# Sensor_Current__INA21X_INA199AX.net
KiCad netlist of a schematic drawn in EAGLE
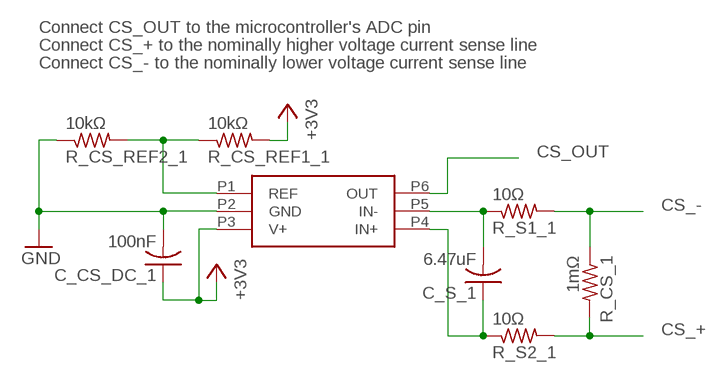
[diagram p0: schematic, sheet 1]

(export (version "E")
  (design (tool "Eeschema 10.0.6"))
  (components
    (comp (ref "CS_1")
      (value "INA21X")
      (footprint "eagle-import:SC70")
      (libsource (lib "eagle-import") (part "INA21X"))
    )
    (comp (ref "C_CS_DC_1")
      (value "100nF")
      (footprint "eagle-import:C0603")
      (libsource (lib "eagle-import") (part "C-USC0603"))
    )
    (comp (ref "C_S_1")
      (value "6.47uF")
      (footprint "eagle-import:C0603")
      (libsource (lib "eagle-import") (part "C-USC0603"))
    )
    (comp (ref "R_CS_1")
      (value "1mΩ")
      (footprint "eagle-import:R1206")
      (libsource (lib "eagle-import") (part "R-US_R1206"))
    )
    (comp (ref "R_CS_REF1_1")
      (value "10kΩ")
      (footprint "eagle-import:R0603")
      (libsource (lib "eagle-import") (part "R-US_R0603"))
    )
    (comp (ref "R_CS_REF2_1")
      (value "10kΩ")
      (footprint "eagle-import:R0603")
      (libsource (lib "eagle-import") (part "R-US_R0603"))
    )
    (comp (ref "R_S1_1")
      (value "10Ω")
      (footprint "eagle-import:R0603")
      (libsource (lib "eagle-import") (part "R-US_R0603"))
    )
    (comp (ref "R_S2_1")
      (value "10Ω")
      (footprint "eagle-import:R0603")
      (libsource (lib "eagle-import") (part "R-US_R0603"))
    )
  )
  (nets
    (net (code "1") (name "+3V3") (class "Default")
      (node (ref "CS_1") (pin "P3") (pinfunction "V+_P3") (pintype "power_in"))
      (node (ref "C_CS_DC_1") (pin "1") (pinfunction "1_1") (pintype "passive"))
      (node (ref "R_CS_REF1_1") (pin "2") (pinfunction "2_2") (pintype "passive"))
    )
    (net (code "2") (name "GND") (class "Default")
      (node (ref "CS_1") (pin "P2") (pinfunction "GND_P2") (pintype "power_in"))
      (node (ref "C_CS_DC_1") (pin "2") (pinfunction "2_2") (pintype "passive"))
      (node (ref "R_CS_REF2_1") (pin "1") (pinfunction "1_1") (pintype "passive"))
    )
    (net (code "3") (name "Net-(CS_1-IN+)") (class "Default")
      (node (ref "CS_1") (pin "P4") (pinfunction "IN+_P4") (pintype "input"))
      (node (ref "C_S_1") (pin "1") (pinfunction "1_1") (pintype "passive"))
      (node (ref "R_S2_1") (pin "1") (pinfunction "1_1") (pintype "passive"))
    )
    (net (code "4") (name "Net-(CS_1-IN-)") (class "Default")
      (node (ref "CS_1") (pin "P5") (pinfunction "IN-_P5") (pintype "input"))
      (node (ref "C_S_1") (pin "2") (pinfunction "2_2") (pintype "passive"))
      (node (ref "R_S1_1") (pin "1") (pinfunction "1_1") (pintype "passive"))
    )
    (net (code "5") (name "Net-(CS_1-REF)") (class "Default")
      (node (ref "CS_1") (pin "P1") (pinfunction "REF_P1") (pintype "input"))
      (node (ref "R_CS_REF1_1") (pin "1") (pinfunction "1_1") (pintype "passive"))
      (node (ref "R_CS_REF2_1") (pin "2") (pinfunction "2_2") (pintype "passive"))
    )
    (net (code "6") (name "Net-(R_CS_1-Pad1)") (class "Default")
      (node (ref "R_CS_1") (pin "1") (pinfunction "1_1") (pintype "passive"))
      (node (ref "R_S1_1") (pin "2") (pinfunction "2_2") (pintype "passive"))
    )
    (net (code "7") (name "Net-(R_CS_1-Pad2)") (class "Default")
      (node (ref "R_CS_1") (pin "2") (pinfunction "2_2") (pintype "passive"))
      (node (ref "R_S2_1") (pin "2") (pinfunction "2_2") (pintype "passive"))
    )
    (net (code "8") (name "unconnected-(CS_1-OUT-PadP6)") (class "Default")
      (node (ref "CS_1") (pin "P6") (pinfunction "OUT_P6") (pintype "output"))
    )
  )
)
